# Power-1.net
KiCad netlist of a schematic drawn in Altium Designer
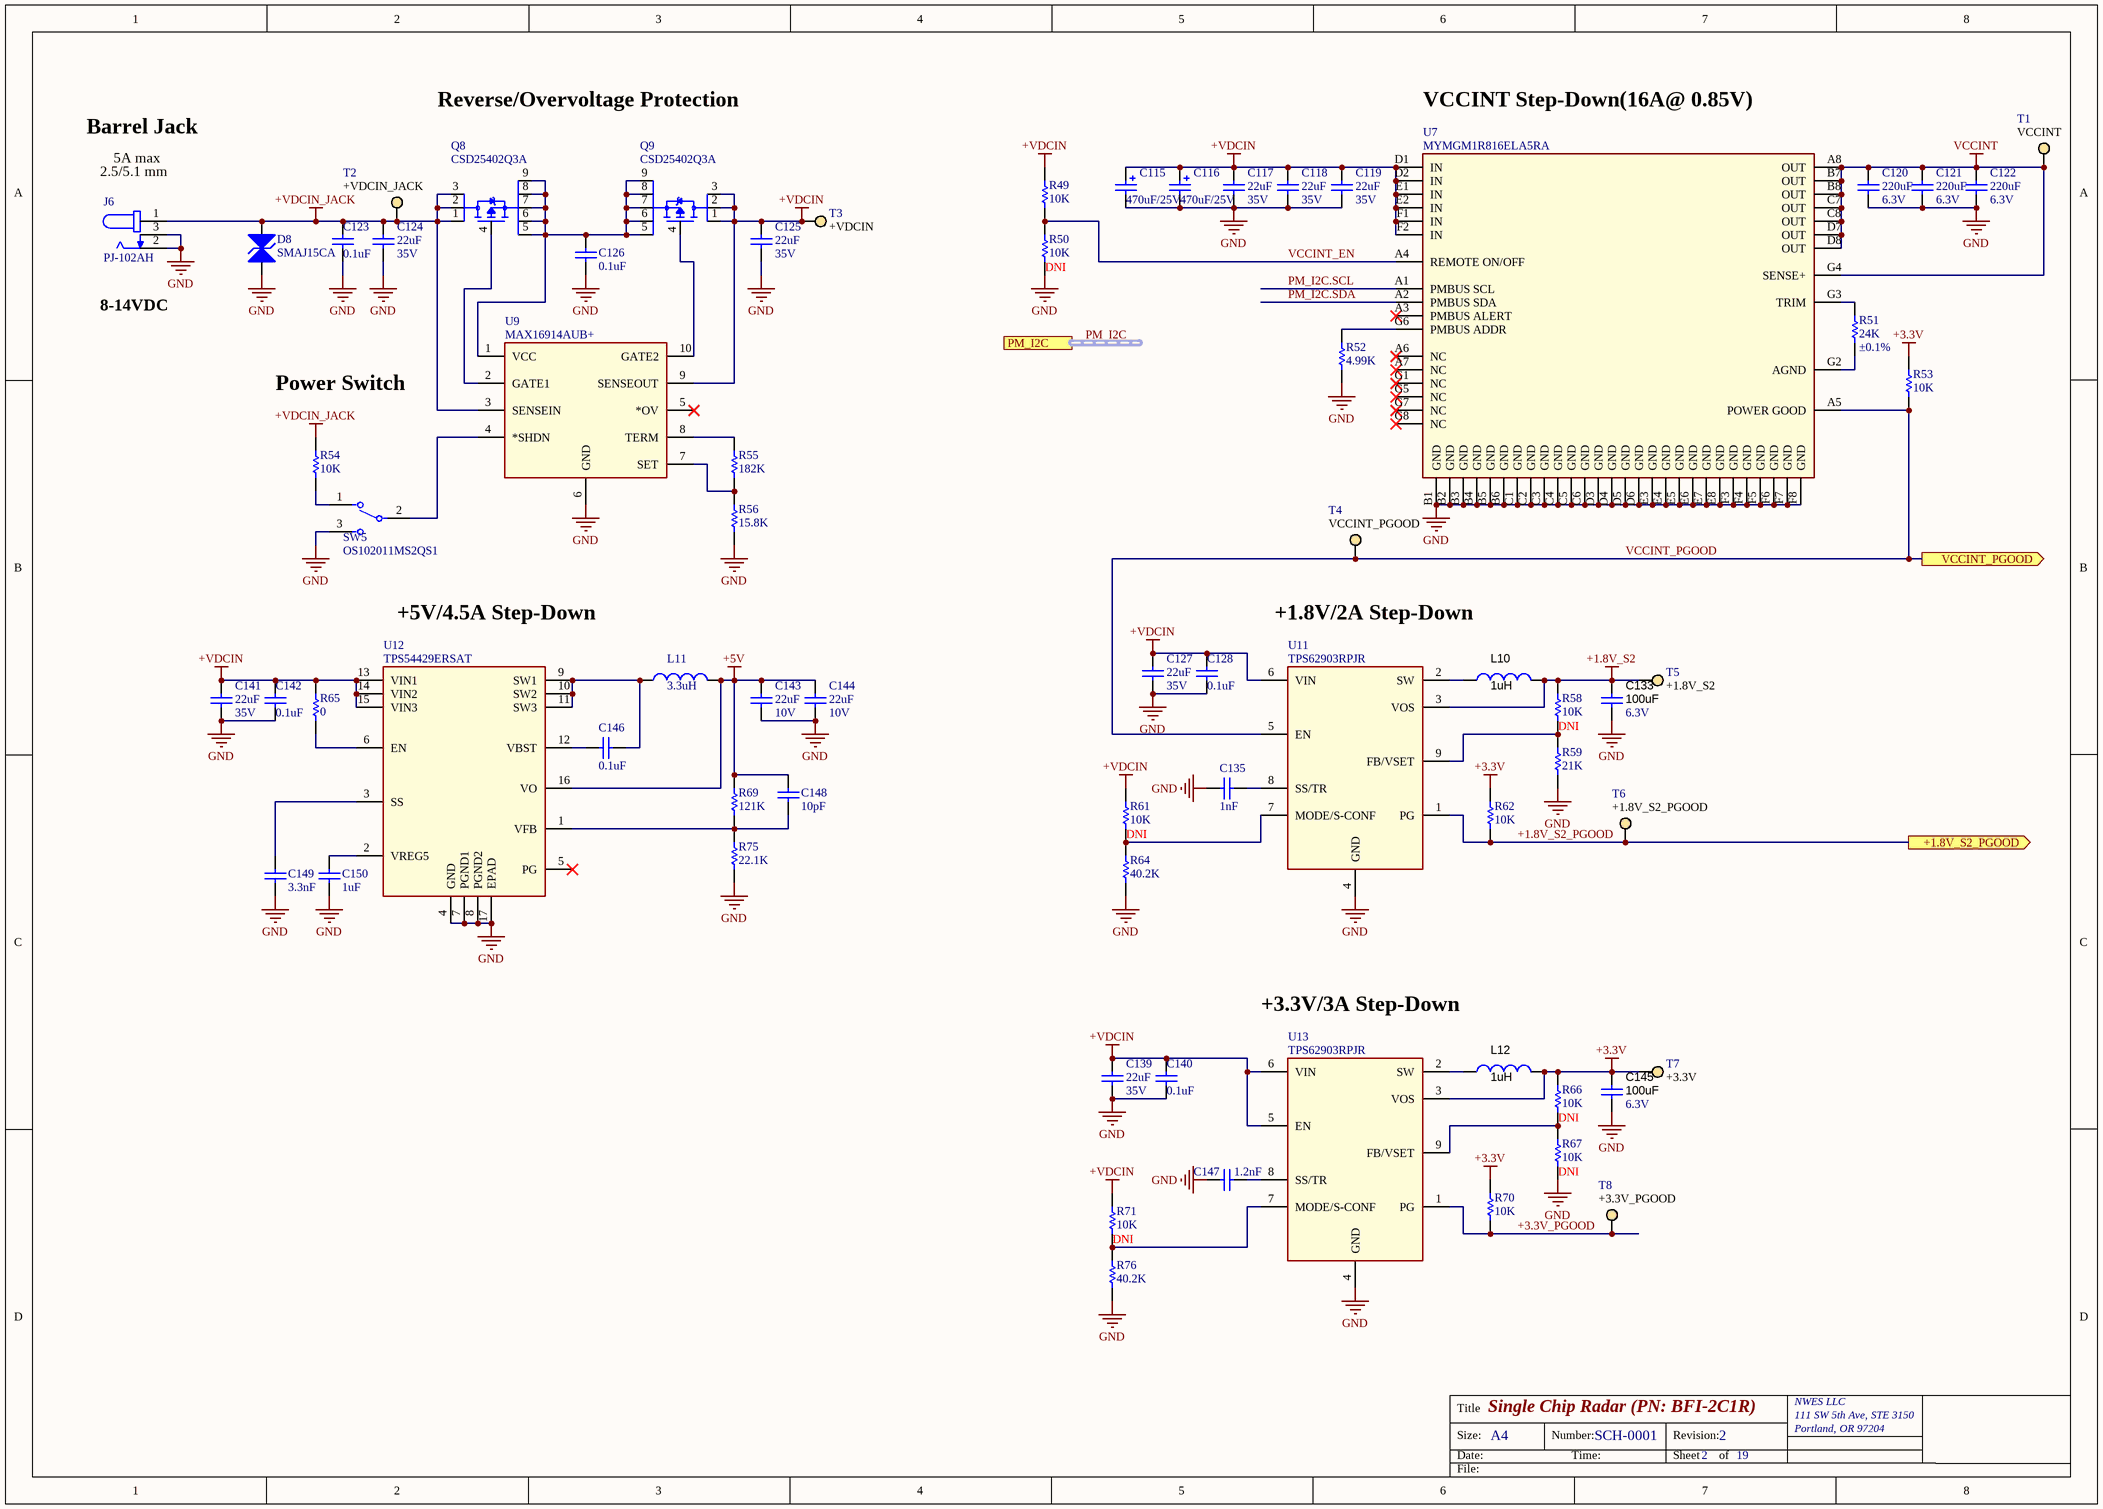
[diagram p0: Power-1.SchDoc]

(export (version "E")
  (design (tool "Eeschema 10.0.6"))
  (components
    (comp (ref "C115")
      (value "470uF/25V")
      (footprint "Panasonic EEE Size G")
      (description "Conductive Polymer Hybrid Aluminum Electrolytic Capacitors, 470µF, 25V, -55 to 125¡C")
      (fields
        (field (name "MANUFACTURER") "Panasonic")
        (field (name "MANUFACTURER PART NUMBER") "EEHZK1E471P")
      )
      (libsource (lib "Radar FPGA RF") (part "CAP ALUM POLY 470UF 20% 25V SMD"))
    )
    (comp (ref "C116")
      (value "470uF/25V")
      (footprint "Panasonic EEE Size G")
      (description "Conductive Polymer Hybrid Aluminum Electrolytic Capacitors, 470µF, 25V, -55 to 125¡C")
      (fields
        (field (name "MANUFACTURER") "Panasonic")
        (field (name "MANUFACTURER PART NUMBER") "EEHZK1E471P")
      )
      (libsource (lib "Radar FPGA RF") (part "CAP ALUM POLY 470UF 20% 25V SMD"))
    )
    (comp (ref "C117")
      (value "22uF")
      (footprint "CAPC3216X180N")
      (description "C Series 1206 22 uF 35 V ±20 % Tolerance X5R SMT Multilayer Ceramic Capacitor")
      (fields
        (field (name "MANUFACTURER") "TDK")
        (field (name "MANUFACTURER PART NUMBER") "C3216X5R1V226M160AC")
        (field (name "VOLTAGE RATING") "35V")
      )
      (libsource (lib "Radar FPGA RF") (part "CAP CER 22UF 35V X5R 1206"))
    )
    (comp (ref "C118")
      (value "22uF")
      (footprint "CAPC3216X180N")
      (description "C Series 1206 22 uF 35 V ±20 % Tolerance X5R SMT Multilayer Ceramic Capacitor")
      (fields
        (field (name "MANUFACTURER") "TDK")
        (field (name "MANUFACTURER PART NUMBER") "C3216X5R1V226M160AC")
        (field (name "VOLTAGE RATING") "35V")
      )
      (libsource (lib "Radar FPGA RF") (part "CAP CER 22UF 35V X5R 1206"))
    )
    (comp (ref "C119")
      (value "22uF")
      (footprint "CAPC3216X180N")
      (description "C Series 1206 22 uF 35 V ±20 % Tolerance X5R SMT Multilayer Ceramic Capacitor")
      (fields
        (field (name "MANUFACTURER") "TDK")
        (field (name "MANUFACTURER PART NUMBER") "C3216X5R1V226M160AC")
        (field (name "VOLTAGE RATING") "35V")
      )
      (libsource (lib "Radar FPGA RF") (part "CAP CER 22UF 35V X5R 1206"))
    )
    (comp (ref "C120")
      (value "220uF")
      (footprint "CAPC3216X180N")
      (description "1206 220 uF 6.3 V ±20% Tolernace X5R Multilayer Ceramic Capacitor")
      (fields
        (field (name "MANUFACTURER") "Murata")
        (field (name "MANUFACTURER PART NUMBER") "GRM31CR60J227ME11L")
        (field (name "VOLTAGE RATING (DC)") "6.3V")
      )
      (libsource (lib "Radar FPGA RF") (part "CAP CER 220UF 6.3V X5R 1206"))
    )
    (comp (ref "C121")
      (value "220uF")
      (footprint "CAPC3216X180N")
      (description "1206 220 uF 6.3 V ±20% Tolernace X5R Multilayer Ceramic Capacitor")
      (fields
        (field (name "MANUFACTURER") "Murata")
        (field (name "MANUFACTURER PART NUMBER") "GRM31CR60J227ME11L")
        (field (name "VOLTAGE RATING (DC)") "6.3V")
      )
      (libsource (lib "Radar FPGA RF") (part "CAP CER 220UF 6.3V X5R 1206"))
    )
    (comp (ref "C122")
      (value "220uF")
      (footprint "CAPC3216X180N")
      (description "1206 220 uF 6.3 V ±20% Tolernace X5R Multilayer Ceramic Capacitor")
      (fields
        (field (name "MANUFACTURER") "Murata")
        (field (name "MANUFACTURER PART NUMBER") "GRM31CR60J227ME11L")
        (field (name "VOLTAGE RATING (DC)") "6.3V")
      )
      (libsource (lib "Radar FPGA RF") (part "CAP CER 220UF 6.3V X5R 1206"))
    )
    (comp (ref "C123")
      (value "0.1uF")
      (footprint "CAPC1005X55USR")
      (description "CAP CER 0.1UF 25V X5R 0402")
      (fields
        (field (name "MANUFACTURER PART NUMBER") "CL05A104KA5NNNC")
        (field (name "MANUFACTURER") "Samsung Electro-Mechanics")
      )
      (libsource (lib "Radar FPGA RF") (part "CAP CER 0.1UF 25V X5R 0402"))
    )
    (comp (ref "C124")
      (value "22uF")
      (footprint "CAPC3216X180N")
      (description "C Series 1206 22 uF 35 V ±20 % Tolerance X5R SMT Multilayer Ceramic Capacitor")
      (fields
        (field (name "MANUFACTURER") "TDK")
        (field (name "MANUFACTURER PART NUMBER") "C3216X5R1V226M160AC")
        (field (name "VOLTAGE RATING") "35V")
      )
      (libsource (lib "Radar FPGA RF") (part "CAP CER 22UF 35V X5R 1206"))
    )
    (comp (ref "C125")
      (value "22uF")
      (footprint "CAPC3216X180N")
      (description "C Series 1206 22 uF 35 V ±20 % Tolerance X5R SMT Multilayer Ceramic Capacitor")
      (fields
        (field (name "MANUFACTURER") "TDK")
        (field (name "MANUFACTURER PART NUMBER") "C3216X5R1V226M160AC")
        (field (name "VOLTAGE RATING") "35V")
      )
      (libsource (lib "Radar FPGA RF") (part "CAP CER 22UF 35V X5R 1206"))
    )
    (comp (ref "C126")
      (value "0.1uF")
      (footprint "CAPC1005X55USR")
      (description "CAP CER 0.1UF 25V X5R 0402")
      (fields
        (field (name "MANUFACTURER PART NUMBER") "CL05A104KA5NNNC")
        (field (name "MANUFACTURER") "Samsung Electro-Mechanics")
      )
      (libsource (lib "Radar FPGA RF") (part "CAP CER 0.1UF 25V X5R 0402"))
    )
    (comp (ref "C127")
      (value "22uF")
      (footprint "CAPC3216X180N")
      (description "C Series 1206 22 uF 35 V ±20 % Tolerance X5R SMT Multilayer Ceramic Capacitor")
      (fields
        (field (name "MANUFACTURER") "TDK")
        (field (name "MANUFACTURER PART NUMBER") "C3216X5R1V226M160AC")
        (field (name "VOLTAGE RATING") "35V")
      )
      (libsource (lib "Radar FPGA RF") (part "CAP CER 22UF 35V X5R 1206"))
    )
    (comp (ref "C128")
      (value "0.1uF")
      (footprint "CAPC1005X55USR")
      (description "CAP CER 0.1UF 25V X5R 0402")
      (fields
        (field (name "MANUFACTURER PART NUMBER") "CL05A104KA5NNNC")
        (field (name "MANUFACTURER") "Samsung Electro-Mechanics")
      )
      (libsource (lib "Radar FPGA RF") (part "CAP CER 0.1UF 25V X5R 0402"))
    )
    (comp (ref "C133")
      (value "100uF")
      (footprint "CAPC3216X180N")
      (description "1206 100 uF 6.3 V ±20% Tolerance X5R SMT Multilayer Ceramic Capacitor")
      (fields
        (field (name "MANUFACTURER") "Murata")
        (field (name "MANUFACTURER PART NUMBER") "GRM31CR60J107ME39L")
        (field (name "VOLTAGE RATING (DC)") "6.3V")
      )
      (libsource (lib "Radar FPGA RF") (part "CAP CER 100UF 6.3V X5R 1206"))
    )
    (comp (ref "C135")
      (value "1nF")
      (footprint "CAPC1005X55USR")
      (description "0402 1000 pF 50 V ±5% Tolerance C0G Multilayer Ceramic Chip Capacitor")
      (fields
        (field (name "MANUFACTURER") "Murata")
        (field (name "MANUFACTURER PART NUMBER") "GRM1555C1H102JA01D")
      )
      (libsource (lib "Radar FPGA RF") (part "CAP CER 1000PF 50V C0G/NP0 0402"))
    )
    (comp (ref "C139")
      (value "22uF")
      (footprint "CAPC3216X180N")
      (description "C Series 1206 22 uF 35 V ±20 % Tolerance X5R SMT Multilayer Ceramic Capacitor")
      (fields
        (field (name "MANUFACTURER") "TDK")
        (field (name "MANUFACTURER PART NUMBER") "C3216X5R1V226M160AC")
        (field (name "VOLTAGE RATING") "35V")
      )
      (libsource (lib "Radar FPGA RF") (part "CAP CER 22UF 35V X5R 1206"))
    )
    (comp (ref "C140")
      (value "0.1uF")
      (footprint "CAPC1005X55USR")
      (description "CAP CER 0.1UF 25V X5R 0402")
      (fields
        (field (name "MANUFACTURER PART NUMBER") "CL05A104KA5NNNC")
        (field (name "MANUFACTURER") "Samsung Electro-Mechanics")
      )
      (libsource (lib "Radar FPGA RF") (part "CAP CER 0.1UF 25V X5R 0402"))
    )
    (comp (ref "C141")
      (value "22uF")
      (footprint "CAPC3216X180N")
      (description "C Series 1206 22 uF 35 V ±20 % Tolerance X5R SMT Multilayer Ceramic Capacitor")
      (fields
        (field (name "MANUFACTURER") "TDK")
        (field (name "MANUFACTURER PART NUMBER") "C3216X5R1V226M160AC")
        (field (name "VOLTAGE RATING") "35V")
      )
      (libsource (lib "Radar FPGA RF") (part "CAP CER 22UF 35V X5R 1206"))
    )
    (comp (ref "C142")
      (value "0.1uF")
      (footprint "CAPC1005X55USR")
      (description "CAP CER 0.1UF 25V X5R 0402")
      (fields
        (field (name "MANUFACTURER PART NUMBER") "CL05A104KA5NNNC")
        (field (name "MANUFACTURER") "Samsung Electro-Mechanics")
      )
      (libsource (lib "Radar FPGA RF") (part "CAP CER 0.1UF 25V X5R 0402"))
    )
    (comp (ref "C143")
      (value "22uF")
      (footprint "CAPC1608X100N")
      (description "Multilayer Ceramic Capacitor, 22 uF, 10 V, ± 20%, X5R, 0603 [1608 Metric]")
      (fields
        (field (name "MANUFACTURER") "TDK")
        (field (name "MANUFACTURER PART NUMBER") "C1608X5R1A226M080AC")
        (field (name "VOLTAGE RATING") "10V")
      )
      (libsource (lib "Radar FPGA RF") (part "CAP CER 22UF 10V X5R 0603"))
    )
    (comp (ref "C144")
      (value "22uF")
      (footprint "CAPC1608X100N")
      (description "Multilayer Ceramic Capacitor, 22 uF, 10 V, ± 20%, X5R, 0603 [1608 Metric]")
      (fields
        (field (name "MANUFACTURER") "TDK")
        (field (name "MANUFACTURER PART NUMBER") "C1608X5R1A226M080AC")
        (field (name "VOLTAGE RATING") "10V")
      )
      (libsource (lib "Radar FPGA RF") (part "CAP CER 22UF 10V X5R 0603"))
    )
    (comp (ref "C145")
      (value "100uF")
      (footprint "CAPC3216X180N")
      (description "1206 100 uF 6.3 V ±20% Tolerance X5R SMT Multilayer Ceramic Capacitor")
      (fields
        (field (name "MANUFACTURER") "Murata")
        (field (name "MANUFACTURER PART NUMBER") "GRM31CR60J107ME39L")
        (field (name "VOLTAGE RATING (DC)") "6.3V")
      )
      (libsource (lib "Radar FPGA RF") (part "CAP CER 100UF 6.3V X5R 1206"))
    )
    (comp (ref "C146")
      (value "0.1uF")
      (footprint "CAPC1005X55USR")
      (description "CAP CER 0.1UF 25V X5R 0402")
      (fields
        (field (name "MANUFACTURER PART NUMBER") "CL05A104KA5NNNC")
        (field (name "MANUFACTURER") "Samsung Electro-Mechanics")
      )
      (libsource (lib "Radar FPGA RF") (part "CAP CER 0.1UF 25V X5R 0402"))
    )
    (comp (ref "C147")
      (value "1.2nF")
      (footprint "CAPC1005X55USR")
      (description "0402 1.2 nF 50 V ±10% Tolerance X7R SMT Multilayer Ceramic Capacitor")
      (fields
        (field (name "MANUFACTURER") "Murata")
        (field (name "MANUFACTURER PART NUMBER") "GRM155R71H122KA01D")
      )
      (libsource (lib "Radar FPGA RF") (part "CAP CER 1200PF 50V X7R 0402"))
    )
    (comp (ref "C148")
      (value "10pF")
      (footprint "CAPC1005X55USR")
      (description "0402 10 pF 50 V ±5% Tolerance C0G SMT Multilayer Ceramic Capacitor")
      (fields
        (field (name "MANUFACTURER") "Murata")
        (field (name "MANUFACTURER PART NUMBER") "GRM1555C1H100JA01D")
      )
      (libsource (lib "Radar FPGA RF") (part "CAP CER 10PF 50V C0G/NP0 0402"))
    )
    (comp (ref "C149")
      (value "3.3nF")
      (footprint "CAPC1005X55USR")
      (description "0402 3.3 nF 50 V ±10% Tolerance X7R SMT Multilayer Ceramic Capacitor")
      (fields
        (field (name "MANUFACTURER") "Murata")
        (field (name "MANUFACTURER PART NUMBER") "GRM155R71H332KA01D")
      )
      (libsource (lib "Radar FPGA RF") (part "CAP CER 3300PF 50V X7R 0402"))
    )
    (comp (ref "C150")
      (value "1uF")
      (footprint "CAPC1005X55USR")
      (description "CAP CER 1UF 25V X5R 0402")
      (fields
        (field (name "MANUFACTURER PART NUMBER") "GRM155R61E105MA12D")
        (field (name "MANUFACTURER") "Murata Electronics")
      )
      (libsource (lib "Radar FPGA RF") (part "CAP CER 1UF 25V X5R 0402"))
    )
    (comp (ref "D8")
      (value "SMAJ15CA")
      (footprint "DIODE DO-214AC(SMA)")
      (description "Diode TVS Single Uni-Dir/Bi-Dir 15V 400W 2-Pin SMA Carrier T/R")
      (fields (field (name "MANUFACTURER") "Littelfuse"))
      (libsource (lib "XEM8320") (part "D_TVS_SMAJ15CA"))
    )
    (comp (ref "J6")
      (value "PJ-102AH")
      (footprint "CUI_PJ-102AH")
      (description "2.0 x 6.5 mm, 5.0 A, Horizontal, Through Hole, Tapered Pins, Dc Power Jack Connector")
      (fields (field (name "MANUFACTURER") "CUI"))
      (libsource (lib "XEM8320") (part "PJ-102AH"))
    )
    (comp (ref "L10")
      (value "1uH")
      (footprint "DFE252012P")
      (description "Inductor Power Chip Shielded Wirewound 1uH 20% 1MHz Metal 3.3A 0.04Ohm DCR 1008 T/R")
      (fields
        (field (name "MANUFACTURER") "Murata")
        (field (name "MANUFACTURER PART NUMBER") "DFE252012F-1R0M=P2")
      )
      (libsource (lib "Radar FPGA RF") (part "FIXED IND 1UH 3.3A 40 MOHM SMD"))
    )
    (comp (ref "L11")
      (value "3.3uH")
      (footprint "IND_IHLP-3232DZ_VIS")
      (description "Inductor Power Shielded Wirewound 3.3uH 20% 100KHz Powdered Iron 9.2A 17.7mOhm DCR 3232 T/R")
      (fields
        (field (name "MANUFACTURER") "Vishay Dale")
        (field (name "MANUFACTURER PART NUMBER") "IHLP3232DZER3R3M01")
        (field (name "INDUCTANCE") "3.3uH")
      )
      (libsource (lib "Radar FPGA RF") (part "FIXED IND 3.3UH 9.2A 17.7MOHM SM"))
    )
    (comp (ref "L12")
      (value "1uH")
      (footprint "DFE252012P")
      (description "Inductor Power Chip Shielded Wirewound 1uH 20% 1MHz Metal 3.3A 0.04Ohm DCR 1008 T/R")
      (fields
        (field (name "MANUFACTURER") "Murata")
        (field (name "MANUFACTURER PART NUMBER") "DFE252012F-1R0M=P2")
      )
      (libsource (lib "Radar FPGA RF") (part "FIXED IND 1UH 3.3A 40 MOHM SMD"))
    )
    (comp (ref "Q8")
      (value "CSD25402Q3A")
      (footprint "8-VSONP (3x3.15)")
      (description "MOSFET P-CH 20V 72A 8SON")
      (fields (field (name "MANUFACTURER") "Texas Instruments"))
      (libsource (lib "XEM8320") (part "CSD25402Q3A"))
    )
    (comp (ref "Q9")
      (value "CSD25402Q3A")
      (footprint "8-VSONP (3x3.15)")
      (description "MOSFET P-CH 20V 72A 8SON")
      (fields (field (name "MANUFACTURER") "Texas Instruments"))
      (libsource (lib "XEM8320") (part "CSD25402Q3A"))
    )
    (comp (ref "R49")
      (value "10K")
      (footprint "RESC1005X40USR")
      (description "RES 10K OHM 1% 1/16W 0402")
      (fields
        (field (name "MANUFACTURER") "YAGEO")
        (field (name "MANUFACTURER PART NUMBER") "RC0402FR-0710KL")
      )
      (libsource (lib "Radar FPGA RF") (part "RES 10K OHM 1% 1/16W 0402"))
    )
    (comp (ref "R50")
      (value "10K")
      (footprint "RESC1005X40USR")
      (description "RES 10K OHM 1% 1/16W 0402")
      (fields
        (field (name "MANUFACTURER") "YAGEO")
        (field (name "MANUFACTURER PART NUMBER") "RC0402FR-0710KL")
      )
      (libsource (lib "Radar FPGA RF") (part "RES 10K OHM 1% 1/16W 0402"))
    )
    (comp (ref "R51")
      (value "24K")
      (footprint "RESC1005X40USR")
      (description "RES SMD 24K OHM 0.1% 1/16W 0402")
      (fields
        (field (name "MANUFACTURER") "YAGEO")
        (field (name "MANUFACTURER PART NUMBER") "RT0402BRE0724KL")
        (field (name "TOLERANCE") "±0.1%")
      )
      (libsource (lib "Radar FPGA RF") (part "RES 24K OHM 0.1% 1/16W 0402"))
    )
    (comp (ref "R52")
      (value "4.99K")
      (footprint "RESC1005X40USR")
      (description "RES 4.99K OHM 1% 1/16W 0402")
      (fields
        (field (name "MANUFACTURER") "YAGEO")
        (field (name "MANUFACTURER PART NUMBER") "RC0402FR-074K99L")
      )
      (libsource (lib "Radar FPGA RF") (part "RES 4.99K OHM 1% 1/16W 0402"))
    )
    (comp (ref "R53")
      (value "10K")
      (footprint "RESC1005X40USR")
      (description "RES 10K OHM 1% 1/16W 0402")
      (fields
        (field (name "MANUFACTURER") "YAGEO")
        (field (name "MANUFACTURER PART NUMBER") "RC0402FR-0710KL")
      )
      (libsource (lib "Radar FPGA RF") (part "RES 10K OHM 1% 1/16W 0402"))
    )
    (comp (ref "R54")
      (value "10K")
      (footprint "RESC1005X40USR")
      (description "RES 10K OHM 1% 1/16W 0402")
      (fields
        (field (name "MANUFACTURER") "YAGEO")
        (field (name "MANUFACTURER PART NUMBER") "RC0402FR-0710KL")
      )
      (libsource (lib "Radar FPGA RF") (part "RES 10K OHM 1% 1/16W 0402"))
    )
    (comp (ref "R55")
      (value "182K")
      (footprint "RESC1005X40USR")
      (description "RES 182K OHM 1% 1/16W 0402")
      (fields
        (field (name "MANUFACTURER") "YAGEO")
        (field (name "MANUFACTURER PART NUMBER") "RC0402FR-07182KL")
      )
      (libsource (lib "Radar FPGA RF") (part "RES 182K OHM 1% 1/16W 0402"))
    )
    (comp (ref "R56")
      (value "15.8K")
      (footprint "RESC1005X40USR")
      (description "RES 15.8K OHM 1% 1/16W 0402")
      (fields
        (field (name "MANUFACTURER") "YAGEO")
        (field (name "MANUFACTURER PART NUMBER") "RC0402FR-0715K8L")
      )
      (libsource (lib "Radar FPGA RF") (part "RES 15.8K OHM 1% 1/16W 0402"))
    )
    (comp (ref "R58")
      (value "10K")
      (footprint "RESC1005X40USR")
      (description "RES 10K OHM 1% 1/16W 0402")
      (fields
        (field (name "MANUFACTURER") "YAGEO")
        (field (name "MANUFACTURER PART NUMBER") "RC0402FR-0710KL")
      )
      (libsource (lib "Radar FPGA RF") (part "RES 10K OHM 1% 1/16W 0402"))
    )
    (comp (ref "R59")
      (value "21K")
      (footprint "RESC1005X40USR")
      (description "RES 21K OHM 1% 1/16W 0402")
      (fields
        (field (name "MANUFACTURER") "YAGEO")
        (field (name "MANUFACTURER PART NUMBER") "RC0402FR-0721KL")
      )
      (libsource (lib "Radar FPGA RF") (part "RES 21K OHM 1% 1/16W 0402"))
    )
    (comp (ref "R61")
      (value "10K")
      (footprint "RESC1005X40USR")
      (description "RES 10K OHM 1% 1/16W 0402")
      (fields
        (field (name "MANUFACTURER") "YAGEO")
        (field (name "MANUFACTURER PART NUMBER") "RC0402FR-0710KL")
      )
      (libsource (lib "Radar FPGA RF") (part "RES 10K OHM 1% 1/16W 0402"))
    )
    (comp (ref "R62")
      (value "10K")
      (footprint "RESC1005X40USR")
      (description "RES 10K OHM 1% 1/16W 0402")
      (fields
        (field (name "MANUFACTURER") "YAGEO")
        (field (name "MANUFACTURER PART NUMBER") "RC0402FR-0710KL")
      )
      (libsource (lib "Radar FPGA RF") (part "RES 10K OHM 1% 1/16W 0402"))
    )
    (comp (ref "R64")
      (value "40.2K")
      (footprint "RESC1005X40USR")
      (description "RES 40.2K OHM 1% 1/16W 0402")
      (fields
        (field (name "MANUFACTURER") "YAGEO")
        (field (name "MANUFACTURER PART NUMBER") "RC0402FR-0740K2L")
      )
      (libsource (lib "Radar FPGA RF") (part "RES 40.2K OHM 1% 1/16W 0402"))
    )
    (comp (ref "R65")
      (value "0")
      (footprint "RESC1005X40USR")
      (description "RES 0 OHM JUMPER 1/16W 0402")
      (fields
        (field (name "MANUFACTURER") "Yageo")
        (field (name "MANUFACTURER PART NUMBER") "RC0402JR-070RL")
      )
      (libsource (lib "Radar FPGA RF") (part "RES 0 OHM JUMPER 1/16W 0402"))
    )
    (comp (ref "R66")
      (value "10K")
      (footprint "RESC1005X40USR")
      (description "RES 10K OHM 1% 1/16W 0402")
      (fields
        (field (name "MANUFACTURER") "YAGEO")
        (field (name "MANUFACTURER PART NUMBER") "RC0402FR-0710KL")
      )
      (libsource (lib "Radar FPGA RF") (part "RES 10K OHM 1% 1/16W 0402"))
    )
    (comp (ref "R67")
      (value "10K")
      (footprint "RESC1005X40USR")
      (description "RES 10K OHM 1% 1/16W 0402")
      (fields
        (field (name "MANUFACTURER") "YAGEO")
        (field (name "MANUFACTURER PART NUMBER") "RC0402FR-0710KL")
      )
      (libsource (lib "Radar FPGA RF") (part "RES 10K OHM 1% 1/16W 0402"))
    )
    (comp (ref "R69")
      (value "121K")
      (footprint "RESC1005X40USR")
      (description "RES 121K OHM 1% 1/16W 0402")
      (fields
        (field (name "MANUFACTURER") "YAGEO")
        (field (name "MANUFACTURER PART NUMBER") "RC0402FR-07121KL")
      )
      (libsource (lib "Radar FPGA RF") (part "RES 121K OHM 1% 1/16W 0402"))
    )
    (comp (ref "R70")
      (value "10K")
      (footprint "RESC1005X40USR")
      (description "RES 10K OHM 1% 1/16W 0402")
      (fields
        (field (name "MANUFACTURER") "YAGEO")
        (field (name "MANUFACTURER PART NUMBER") "RC0402FR-0710KL")
      )
      (libsource (lib "Radar FPGA RF") (part "RES 10K OHM 1% 1/16W 0402"))
    )
    (comp (ref "R71")
      (value "10K")
      (footprint "RESC1005X40USR")
      (description "RES 10K OHM 1% 1/16W 0402")
      (fields
        (field (name "MANUFACTURER") "YAGEO")
        (field (name "MANUFACTURER PART NUMBER") "RC0402FR-0710KL")
      )
      (libsource (lib "Radar FPGA RF") (part "RES 10K OHM 1% 1/16W 0402"))
    )
    (comp (ref "R75")
      (value "22.1K")
      (footprint "RESC1005X40USR")
      (description "RES 22.1K OHM 1% 1/16W 0402")
      (fields
        (field (name "MANUFACTURER") "YAGEO")
        (field (name "MANUFACTURER PART NUMBER") "RC0402FR-0722K1L")
      )
      (libsource (lib "Radar FPGA RF") (part "RES 22.1K OHM 1% 1/16W 0402"))
    )
    (comp (ref "R76")
      (value "40.2K")
      (footprint "RESC1005X40USR")
      (description "RES 40.2K OHM 1% 1/16W 0402")
      (fields
        (field (name "MANUFACTURER") "YAGEO")
        (field (name "MANUFACTURER PART NUMBER") "RC0402FR-0740K2L")
      )
      (libsource (lib "Radar FPGA RF") (part "RES 40.2K OHM 1% 1/16W 0402"))
    )
    (comp (ref "SW5")
      (value "OS102011MS2QS1")
      (footprint "SW_OS102011MS2QS1")
      (description "Switch Slide ON ON SPDT Top Slide 0.1A 12VDC 10000Cycle PC Pins Bracket Mount/Through Hole Bulk")
      (fields (field (name "MANUFACTURER") "ITT C&K"))
      (libsource (lib "XEM8320") (part "SW_OS102011MS2QS1"))
    )
    (comp (ref "T1")
      (value "TP_S")
      (footprint "TP_SM_1MM")
      (description "test point")
      (fields (field (name "PARAMETER 1") "VCCINT"))
      (libsource (lib "Radar FPGA RF") (part "Test point PAD"))
    )
    (comp (ref "T2")
      (value "TP_S")
      (footprint "TP_SM_1MM")
      (description "test point")
      (fields (field (name "PARAMETER 1") "+VDCIN_JACK"))
      (libsource (lib "Radar FPGA RF") (part "Test point PAD"))
    )
    (comp (ref "T3")
      (value "TP_S")
      (footprint "TP_SM_1MM")
      (description "test point")
      (fields (field (name "PARAMETER 1") "+VDCIN"))
      (libsource (lib "Radar FPGA RF") (part "Test point PAD"))
    )
    (comp (ref "T4")
      (value "TP_S")
      (footprint "TP_SM_1MM")
      (description "test point")
      (fields (field (name "PARAMETER 1") "VCCINT_PGOOD"))
      (libsource (lib "Radar FPGA RF") (part "Test point PAD"))
    )
    (comp (ref "T5")
      (value "TP_S")
      (footprint "TP_SM_1MM")
      (description "test point")
      (fields (field (name "PARAMETER 1") "+1.8V_S2"))
      (libsource (lib "Radar FPGA RF") (part "Test point PAD"))
    )
    (comp (ref "T6")
      (value "TP_S")
      (footprint "TP_SM_1MM")
      (description "test point")
      (fields (field (name "PARAMETER 1") "+1.8V_S2_PGOOD"))
      (libsource (lib "Radar FPGA RF") (part "Test point PAD"))
    )
    (comp (ref "T7")
      (value "TP_S")
      (footprint "TP_SM_1MM")
      (description "test point")
      (fields (field (name "PARAMETER 1") "+3.3V"))
      (libsource (lib "Radar FPGA RF") (part "Test point PAD"))
    )
    (comp (ref "T8")
      (value "TP_S")
      (footprint "TP_SM_1MM")
      (description "test point")
      (fields (field (name "PARAMETER 1") "+3.3V_PGOOD"))
      (libsource (lib "Radar FPGA RF") (part "Test point PAD"))
    )
    (comp (ref "U7")
      (value "MYMGM1R816ELA5RA")
      (footprint "56-SMD Module")
      (description "Non-Isolated PoL Module DC DC Converter 1 Output 0.7 ~ 1.8V 16A 7.5V - 15V Input")
      (fields (field (name "MANUFACTURER") "Murata"))
      (libsource (lib "XEM8320") (part "MYMGM1R816ELA5RA"))
    )
    (comp (ref "U9")
      (value "MAX16914AUB+")
      (footprint "10-TFSOP")
      (description "Ideal Diode, Reverse-Battery, and Overvoltage Protection Switch/Limiter Controll")
      (fields (field (name "MANUFACTURER") "Maxim"))
      (libsource (lib "XEM8320") (part "MAX16914AUB+"))
    )
    (comp (ref "U11")
      (value "TPS62903RPJR")
      (footprint "9-VQFN-HR (1.5x2)")
      (description "3-V TO 17-V, 3-A, HIGH-EFFICIENC")
      (fields (field (name "MANUFACTURER") "Texas Instruments"))
      (libsource (lib "XEM8320") (part "TPS62903RPJR"))
    )
    (comp (ref "U12")
      (value "TPS54429ERSAT")
      (footprint "16-QFN (4x4)")
      (description "IC REG BUCK ADJ 4.5A 16QFN")
      (fields (field (name "MANUFACTURER") "Texas Instruments"))
      (libsource (lib "XEM8320") (part "TPS54429ERSAT"))
    )
    (comp (ref "U13")
      (value "TPS62903RPJR")
      (footprint "9-VQFN-HR (1.5x2)")
      (description "3-V TO 17-V, 3-A, HIGH-EFFICIENC")
      (fields (field (name "MANUFACTURER") "Texas Instruments"))
      (libsource (lib "XEM8320") (part "TPS62903RPJR"))
    )
  )
  (nets
    (net (code "2") (name "+1.8V_S2") (class "Default")
      (node (ref "C133") (pin "1") (pinfunction "1_1") (pintype "passive"))
      (node (ref "L10") (pin "2") (pinfunction "2_2") (pintype "passive"))
      (node (ref "R58") (pin "2") (pinfunction "2_2") (pintype "passive"))
      (node (ref "T5") (pin "1") (pintype "passive"))
      (node (ref "U11") (pin "3") (pinfunction "VOS_3") (pintype "passive"))
    )
    (net (code "3") (name "+3.3V") (class "Default")
      (node (ref "C145") (pin "1") (pinfunction "1_1") (pintype "passive"))
      (node (ref "L12") (pin "2") (pinfunction "2_2") (pintype "passive"))
      (node (ref "R53") (pin "2") (pinfunction "2_2") (pintype "passive"))
      (node (ref "R62") (pin "2") (pinfunction "2_2") (pintype "passive"))
      (node (ref "R66") (pin "2") (pinfunction "2_2") (pintype "passive"))
      (node (ref "R70") (pin "2") (pinfunction "2_2") (pintype "passive"))
      (node (ref "T7") (pin "1") (pintype "passive"))
      (node (ref "U13") (pin "3") (pinfunction "VOS_3") (pintype "passive"))
    )
    (net (code "4") (name "+5V") (class "Default")
      (node (ref "C143") (pin "1") (pinfunction "1_1") (pintype "passive"))
      (node (ref "C144") (pin "1") (pinfunction "1_1") (pintype "passive"))
      (node (ref "C148") (pin "2") (pinfunction "2_2") (pintype "passive"))
      (node (ref "L11") (pin "2") (pinfunction "2_2") (pintype "passive"))
      (node (ref "R69") (pin "2") (pinfunction "2_2") (pintype "passive"))
      (node (ref "U12") (pin "16") (pinfunction "VO_16") (pintype "passive"))
    )
    (net (code "5") (name "+VDCIN") (class "Default")
      (node (ref "C115") (pin "1") (pinfunction "1_1") (pintype "passive"))
      (node (ref "C116") (pin "1") (pinfunction "1_1") (pintype "passive"))
      (node (ref "C117") (pin "1") (pinfunction "1_1") (pintype "passive"))
      (node (ref "C118") (pin "1") (pinfunction "1_1") (pintype "passive"))
      (node (ref "C119") (pin "1") (pinfunction "1_1") (pintype "passive"))
      (node (ref "C125") (pin "1") (pinfunction "1_1") (pintype "passive"))
      (node (ref "C127") (pin "1") (pinfunction "1_1") (pintype "passive"))
      (node (ref "C128") (pin "2") (pinfunction "2_2") (pintype "passive"))
      (node (ref "C139") (pin "1") (pinfunction "1_1") (pintype "passive"))
      (node (ref "C140") (pin "2") (pinfunction "2_2") (pintype "passive"))
      (node (ref "C141") (pin "1") (pinfunction "1_1") (pintype "passive"))
      (node (ref "C142") (pin "2") (pinfunction "2_2") (pintype "passive"))
      (node (ref "Q9") (pin "1") (pinfunction "D_1") (pintype "passive"))
      (node (ref "Q9") (pin "2") (pinfunction "D_2") (pintype "passive"))
      (node (ref "Q9") (pin "3") (pinfunction "D_3") (pintype "passive"))
      (node (ref "R49") (pin "2") (pinfunction "2_2") (pintype "passive"))
      (node (ref "R61") (pin "2") (pinfunction "2_2") (pintype "passive"))
      (node (ref "R65") (pin "2") (pinfunction "2_2") (pintype "passive"))
      (node (ref "R71") (pin "2") (pinfunction "2_2") (pintype "passive"))
      (node (ref "T3") (pin "1") (pintype "passive"))
      (node (ref "U11") (pin "6") (pinfunction "VIN_6") (pintype "passive"))
      (node (ref "U12") (pin "13") (pinfunction "VIN1_13") (pintype "passive"))
      (node (ref "U12") (pin "14") (pinfunction "VIN2_14") (pintype "passive"))
      (node (ref "U12") (pin "15") (pinfunction "VIN3_15") (pintype "passive"))
      (node (ref "U13") (pin "5") (pinfunction "EN_5") (pintype "passive"))
      (node (ref "U13") (pin "6") (pinfunction "VIN_6") (pintype "passive"))
      (node (ref "U7") (pin "D1") (pinfunction "IN_D1") (pintype "passive"))
      (node (ref "U7") (pin "D2") (pinfunction "IN_D2") (pintype "passive"))
      (node (ref "U7") (pin "E1") (pinfunction "IN_E1") (pintype "passive"))
      (node (ref "U7") (pin "E2") (pinfunction "IN_E2") (pintype "passive"))
      (node (ref "U7") (pin "F1") (pinfunction "IN_F1") (pintype "passive"))
      (node (ref "U7") (pin "F2") (pinfunction "IN_F2") (pintype "passive"))
      (node (ref "U9") (pin "9") (pinfunction "SENSEOUT_9") (pintype "passive"))
    )
    (net (code "6") (name "+VDCIN_JACK") (class "Default")
      (node (ref "C123") (pin "2") (pinfunction "2_2") (pintype "passive"))
      (node (ref "C124") (pin "1") (pinfunction "1_1") (pintype "passive"))
      (node (ref "D8") (pin "1") (pinfunction "1_1") (pintype "passive"))
      (node (ref "J6") (pin "1") (pinfunction "1_1") (pintype "passive"))
      (node (ref "Q8") (pin "1") (pinfunction "D_1") (pintype "passive"))
      (node (ref "Q8") (pin "2") (pinfunction "D_2") (pintype "passive"))
      (node (ref "Q8") (pin "3") (pinfunction "D_3") (pintype "passive"))
      (node (ref "R54") (pin "2") (pinfunction "2_2") (pintype "passive"))
      (node (ref "T2") (pin "1") (pintype "passive"))
      (node (ref "U9") (pin "3") (pinfunction "SENSEIN_3") (pintype "passive"))
    )
    (net (code "7") (name "/+1.8V_S2_PGOOD") (class "Default")
      (node (ref "R62") (pin "1") (pinfunction "1_1") (pintype "passive"))
      (node (ref "T6") (pin "1") (pintype "passive"))
      (node (ref "U11") (pin "1") (pinfunction "PG_1") (pintype "passive"))
    )
    (net (code "8") (name "/+3.3V_PGOOD") (class "Default")
      (node (ref "R70") (pin "1") (pinfunction "1_1") (pintype "passive"))
      (node (ref "T8") (pin "1") (pintype "passive"))
      (node (ref "U13") (pin "1") (pinfunction "PG_1") (pintype "passive"))
    )
    (net (code "9") (name "/PM_I2C.SCL") (class "Default")
      (node (ref "U7") (pin "A1") (pinfunction "PMBUS_SCL_A1") (pintype "passive"))
    )
    (net (code "10") (name "/PM_I2C.SDA") (class "Default")
      (node (ref "U7") (pin "A2") (pinfunction "PMBUS_SDA_A2") (pintype "passive"))
    )
    (net (code "11") (name "/VCCINT_EN") (class "Default")
      (node (ref "R49") (pin "1") (pinfunction "1_1") (pintype "passive"))
      (node (ref "R50") (pin "2") (pinfunction "2_2") (pintype "passive"))
      (node (ref "U7") (pin "A4") (pinfunction "REMOTE_ON/OFF_A4") (pintype "passive"))
    )
    (net (code "12") (name "/VCCINT_PGOOD") (class "Default")
      (node (ref "R53") (pin "1") (pinfunction "1_1") (pintype "passive"))
      (node (ref "T4") (pin "1") (pintype "passive"))
      (node (ref "U11") (pin "5") (pinfunction "EN_5") (pintype "passive"))
      (node (ref "U7") (pin "A5") (pinfunction "POWER_GOOD_A5") (pintype "passive"))
    )
    (net (code "14") (name "GND") (class "Default")
      (node (ref "C115") (pin "2") (pinfunction "2_2") (pintype "passive"))
      (node (ref "C116") (pin "2") (pinfunction "2_2") (pintype "passive"))
      (node (ref "C117") (pin "2") (pinfunction "2_2") (pintype "passive"))
      (node (ref "C118") (pin "2") (pinfunction "2_2") (pintype "passive"))
      (node (ref "C119") (pin "2") (pinfunction "2_2") (pintype "passive"))
      (node (ref "C120") (pin "2") (pinfunction "2_2") (pintype "passive"))
      (node (ref "C121") (pin "2") (pinfunction "2_2") (pintype "passive"))
      (node (ref "C122") (pin "2") (pinfunction "2_2") (pintype "passive"))
      (node (ref "C123") (pin "1") (pinfunction "1_1") (pintype "passive"))
      (node (ref "C124") (pin "2") (pinfunction "2_2") (pintype "passive"))
      (node (ref "C125") (pin "2") (pinfunction "2_2") (pintype "passive"))
      (node (ref "C126") (pin "1") (pinfunction "1_1") (pintype "passive"))
      (node (ref "C127") (pin "2") (pinfunction "2_2") (pintype "passive"))
      (node (ref "C128") (pin "1") (pinfunction "1_1") (pintype "passive"))
      (node (ref "C133") (pin "2") (pinfunction "2_2") (pintype "passive"))
      (node (ref "C135") (pin "1") (pinfunction "1_1") (pintype "passive"))
      (node (ref "C139") (pin "2") (pinfunction "2_2") (pintype "passive"))
      (node (ref "C140") (pin "1") (pinfunction "1_1") (pintype "passive"))
      (node (ref "C141") (pin "2") (pinfunction "2_2") (pintype "passive"))
      (node (ref "C142") (pin "1") (pinfunction "1_1") (pintype "passive"))
      (node (ref "C143") (pin "2") (pinfunction "2_2") (pintype "passive"))
      (node (ref "C144") (pin "2") (pinfunction "2_2") (pintype "passive"))
      (node (ref "C145") (pin "2") (pinfunction "2_2") (pintype "passive"))
      (node (ref "C147") (pin "1") (pinfunction "1_1") (pintype "passive"))
      (node (ref "C149") (pin "1") (pinfunction "1_1") (pintype "passive"))
      (node (ref "C150") (pin "1") (pinfunction "1_1") (pintype "passive"))
      (node (ref "D8") (pin "2") (pinfunction "2_2") (pintype "passive"))
      (node (ref "J6") (pin "2") (pinfunction "2_2") (pintype "passive"))
      (node (ref "J6") (pin "3") (pinfunction "3_3") (pintype "passive"))
      (node (ref "R50") (pin "1") (pinfunction "1_1") (pintype "passive"))
      (node (ref "R52") (pin "1") (pinfunction "1_1") (pintype "passive"))
      (node (ref "R56") (pin "1") (pinfunction "1_1") (pintype "passive"))
      (node (ref "R59") (pin "1") (pinfunction "1_1") (pintype "passive"))
      (node (ref "R64") (pin "1") (pinfunction "1_1") (pintype "passive"))
      (node (ref "R67") (pin "1") (pinfunction "1_1") (pintype "passive"))
      (node (ref "R75") (pin "1") (pinfunction "1_1") (pintype "passive"))
      (node (ref "R76") (pin "1") (pinfunction "1_1") (pintype "passive"))
      (node (ref "SW5") (pin "3") (pinfunction "3_3") (pintype "passive"))
      (node (ref "U11") (pin "4") (pinfunction "GND_4") (pintype "passive"))
      (node (ref "U12") (pin "17") (pinfunction "EPAD_17") (pintype "passive"))
      (node (ref "U12") (pin "4") (pinfunction "GND_4") (pintype "passive"))
      (node (ref "U12") (pin "7") (pinfunction "PGND1_7") (pintype "passive"))
      (node (ref "U12") (pin "8") (pinfunction "PGND2_8") (pintype "passive"))
      (node (ref "U13") (pin "4") (pinfunction "GND_4") (pintype "passive"))
      (node (ref "U7") (pin "B1") (pinfunction "GND_B1") (pintype "passive"))
      (node (ref "U7") (pin "B2") (pinfunction "GND_B2") (pintype "passive"))
      (node (ref "U7") (pin "B3") (pinfunction "GND_B3") (pintype "passive"))
      (node (ref "U7") (pin "B4") (pinfunction "GND_B4") (pintype "passive"))
      (node (ref "U7") (pin "B5") (pinfunction "GND_B5") (pintype "passive"))
      (node (ref "U7") (pin "B6") (pinfunction "GND_B6") (pintype "passive"))
      (node (ref "U7") (pin "C1") (pinfunction "GND_C1") (pintype "passive"))
      (node (ref "U7") (pin "C2") (pinfunction "GND_C2") (pintype "passive"))
      (node (ref "U7") (pin "C3") (pinfunction "GND_C3") (pintype "passive"))
      (node (ref "U7") (pin "C4") (pinfunction "GND_C4") (pintype "passive"))
      (node (ref "U7") (pin "C5") (pinfunction "GND_C5") (pintype "passive"))
      (node (ref "U7") (pin "C6") (pinfunction "GND_C6") (pintype "passive"))
      (node (ref "U7") (pin "D3") (pinfunction "GND_D3") (pintype "passive"))
      (node (ref "U7") (pin "D4") (pinfunction "GND_D4") (pintype "passive"))
      (node (ref "U7") (pin "D5") (pinfunction "GND_D5") (pintype "passive"))
      (node (ref "U7") (pin "D6") (pinfunction "GND_D6") (pintype "passive"))
      (node (ref "U7") (pin "E3") (pinfunction "GND_E3") (pintype "passive"))
      (node (ref "U7") (pin "E4") (pinfunction "GND_E4") (pintype "passive"))
      (node (ref "U7") (pin "E5") (pinfunction "GND_E5") (pintype "passive"))
      (node (ref "U7") (pin "E6") (pinfunction "GND_E6") (pintype "passive"))
      (node (ref "U7") (pin "E7") (pinfunction "GND_E7") (pintype "passive"))
      (node (ref "U7") (pin "E8") (pinfunction "GND_E8") (pintype "passive"))
      (node (ref "U7") (pin "F3") (pinfunction "GND_F3") (pintype "passive"))
      (node (ref "U7") (pin "F4") (pinfunction "GND_F4") (pintype "passive"))
      (node (ref "U7") (pin "F5") (pinfunction "GND_F5") (pintype "passive"))
      (node (ref "U7") (pin "F6") (pinfunction "GND_F6") (pintype "passive"))
      (node (ref "U7") (pin "F7") (pinfunction "GND_F7") (pintype "passive"))
      (node (ref "U7") (pin "F8") (pinfunction "GND_F8") (pintype "passive"))
      (node (ref "U9") (pin "6") (pinfunction "GND_6") (pintype "passive"))
    )
    (net (code "15") (name "Net-(Q8-G)") (class "Default")
      (node (ref "Q8") (pin "4") (pinfunction "G_4") (pintype "passive"))
      (node (ref "U9") (pin "2") (pinfunction "GATE1_2") (pintype "passive"))
    )
    (net (code "16") (name "Net-(Q9-G)") (class "Default")
      (node (ref "Q9") (pin "4") (pinfunction "G_4") (pintype "passive"))
      (node (ref "U9") (pin "10") (pinfunction "GATE2_10") (pintype "passive"))
    )
    (net (code "17") (name "Net-(R54-Pad1)") (class "Default")
      (node (ref "R54") (pin "1") (pinfunction "1_1") (pintype "passive"))
      (node (ref "SW5") (pin "1") (pinfunction "1_1") (pintype "passive"))
    )
    (net (code "18") (name "Net-(U7-AGND)") (class "Default")
      (node (ref "R51") (pin "1") (pinfunction "1_1") (pintype "passive"))
      (node (ref "U7") (pin "G2") (pinfunction "AGND_G2") (pintype "passive"))
    )
    (net (code "19") (name "Net-(U7-PMBUS_ADDR)") (class "Default")
      (node (ref "R52") (pin "2") (pinfunction "2_2") (pintype "passive"))
      (node (ref "U7") (pin "G6") (pinfunction "PMBUS_ADDR_G6") (pintype "passive"))
    )
    (net (code "20") (name "Net-(U7-TRIM)") (class "Default")
      (node (ref "R51") (pin "2") (pinfunction "2_2") (pintype "passive"))
      (node (ref "U7") (pin "G3") (pinfunction "TRIM_G3") (pintype "passive"))
    )
    (net (code "21") (name "Net-(U9-*SHDN)") (class "Default")
      (node (ref "SW5") (pin "2") (pinfunction "2_2") (pintype "passive"))
      (node (ref "U9") (pin "4") (pinfunction "*SHDN_4") (pintype "passive"))
    )
    (net (code "22") (name "Net-(U9-SET)") (class "Default")
      (node (ref "R55") (pin "1") (pinfunction "1_1") (pintype "passive"))
      (node (ref "R56") (pin "2") (pinfunction "2_2") (pintype "passive"))
      (node (ref "U9") (pin "7") (pinfunction "SET_7") (pintype "passive"))
    )
    (net (code "23") (name "Net-(U9-TERM)") (class "Default")
      (node (ref "R55") (pin "2") (pinfunction "2_2") (pintype "passive"))
      (node (ref "U9") (pin "8") (pinfunction "TERM_8") (pintype "passive"))
    )
    (net (code "24") (name "Net-(U9-VCC)") (class "Default")
      (node (ref "C126") (pin "2") (pinfunction "2_2") (pintype "passive"))
      (node (ref "Q8") (pin "5") (pinfunction "S_5") (pintype "passive"))
      (node (ref "Q8") (pin "6") (pinfunction "S_6") (pintype "passive"))
      (node (ref "Q8") (pin "7") (pinfunction "S_7") (pintype "passive"))
      (node (ref "Q8") (pin "8") (pinfunction "S_8") (pintype "passive"))
      (node (ref "Q8") (pin "9") (pinfunction "S_9") (pintype "passive"))
      (node (ref "Q9") (pin "5") (pinfunction "S_5") (pintype "passive"))
      (node (ref "Q9") (pin "6") (pinfunction "S_6") (pintype "passive"))
      (node (ref "Q9") (pin "7") (pinfunction "S_7") (pintype "passive"))
      (node (ref "Q9") (pin "8") (pinfunction "S_8") (pintype "passive"))
      (node (ref "Q9") (pin "9") (pinfunction "S_9") (pintype "passive"))
      (node (ref "U9") (pin "1") (pinfunction "VCC_1") (pintype "passive"))
    )
    (net (code "25") (name "Net-(U11-FB{slash}VSET)") (class "Default")
      (node (ref "R58") (pin "1") (pinfunction "1_1") (pintype "passive"))
      (node (ref "R59") (pin "2") (pinfunction "2_2") (pintype "passive"))
      (node (ref "U11") (pin "9") (pinfunction "FB/VSET_9") (pintype "passive"))
    )
    (net (code "26") (name "Net-(U11-MODE{slash}S-CONF)") (class "Default")
      (node (ref "R61") (pin "1") (pinfunction "1_1") (pintype "passive"))
      (node (ref "R64") (pin "2") (pinfunction "2_2") (pintype "passive"))
      (node (ref "U11") (pin "7") (pinfunction "MODE/S-CONF_7") (pintype "passive"))
    )
    (net (code "27") (name "Net-(U11-SS{slash}TR)") (class "Default")
      (node (ref "C135") (pin "2") (pinfunction "2_2") (pintype "passive"))
      (node (ref "U11") (pin "8") (pinfunction "SS/TR_8") (pintype "passive"))
    )
    (net (code "28") (name "Net-(U11-SW)") (class "Default")
      (node (ref "L10") (pin "1") (pinfunction "1_1") (pintype "passive"))
      (node (ref "U11") (pin "2") (pinfunction "SW_2") (pintype "passive"))
    )
    (net (code "29") (name "Net-(U12-EN)") (class "Default")
      (node (ref "R65") (pin "1") (pinfunction "1_1") (pintype "passive"))
      (node (ref "U12") (pin "6") (pinfunction "EN_6") (pintype "passive"))
    )
    (net (code "30") (name "Net-(U12-SS)") (class "Default")
      (node (ref "C149") (pin "2") (pinfunction "2_2") (pintype "passive"))
      (node (ref "U12") (pin "3") (pinfunction "SS_3") (pintype "passive"))
    )
    (net (code "31") (name "Net-(U12-SW1)") (class "Default")
      (node (ref "C146") (pin "1") (pinfunction "1_1") (pintype "passive"))
      (node (ref "L11") (pin "1") (pinfunction "1_1") (pintype "passive"))
      (node (ref "U12") (pin "10") (pinfunction "SW2_10") (pintype "passive"))
      (node (ref "U12") (pin "11") (pinfunction "SW3_11") (pintype "passive"))
      (node (ref "U12") (pin "9") (pinfunction "SW1_9") (pintype "passive"))
    )
    (net (code "32") (name "Net-(U12-VBST)") (class "Default")
      (node (ref "C146") (pin "2") (pinfunction "2_2") (pintype "passive"))
      (node (ref "U12") (pin "12") (pinfunction "VBST_12") (pintype "passive"))
    )
    (net (code "33") (name "Net-(U12-VFB)") (class "Default")
      (node (ref "C148") (pin "1") (pinfunction "1_1") (pintype "passive"))
      (node (ref "R69") (pin "1") (pinfunction "1_1") (pintype "passive"))
      (node (ref "R75") (pin "2") (pinfunction "2_2") (pintype "passive"))
      (node (ref "U12") (pin "1") (pinfunction "VFB_1") (pintype "passive"))
    )
    (net (code "34") (name "Net-(U12-VREG5)") (class "Default")
      (node (ref "C150") (pin "2") (pinfunction "2_2") (pintype "passive"))
      (node (ref "U12") (pin "2") (pinfunction "VREG5_2") (pintype "passive"))
    )
    (net (code "35") (name "Net-(U13-FB{slash}VSET)") (class "Default")
      (node (ref "R66") (pin "1") (pinfunction "1_1") (pintype "passive"))
      (node (ref "R67") (pin "2") (pinfunction "2_2") (pintype "passive"))
      (node (ref "U13") (pin "9") (pinfunction "FB/VSET_9") (pintype "passive"))
    )
    (net (code "36") (name "Net-(U13-MODE{slash}S-CONF)") (class "Default")
      (node (ref "R71") (pin "1") (pinfunction "1_1") (pintype "passive"))
      (node (ref "R76") (pin "2") (pinfunction "2_2") (pintype "passive"))
      (node (ref "U13") (pin "7") (pinfunction "MODE/S-CONF_7") (pintype "passive"))
    )
    (net (code "37") (name "Net-(U13-SS{slash}TR)") (class "Default")
      (node (ref "C147") (pin "2") (pinfunction "2_2") (pintype "passive"))
      (node (ref "U13") (pin "8") (pinfunction "SS/TR_8") (pintype "passive"))
    )
    (net (code "38") (name "Net-(U13-SW)") (class "Default")
      (node (ref "L12") (pin "1") (pinfunction "1_1") (pintype "passive"))
      (node (ref "U13") (pin "2") (pinfunction "SW_2") (pintype "passive"))
    )
    (net (code "39") (name "VCCINT") (class "Default")
      (node (ref "C120") (pin "1") (pinfunction "1_1") (pintype "passive"))
      (node (ref "C121") (pin "1") (pinfunction "1_1") (pintype "passive"))
      (node (ref "C122") (pin "1") (pinfunction "1_1") (pintype "passive"))
      (node (ref "T1") (pin "1") (pintype "passive"))
      (node (ref "U7") (pin "A8") (pinfunction "OUT_A8") (pintype "passive"))
      (node (ref "U7") (pin "B7") (pinfunction "OUT_B7") (pintype "passive"))
      (node (ref "U7") (pin "B8") (pinfunction "OUT_B8") (pintype "passive"))
      (node (ref "U7") (pin "C7") (pinfunction "OUT_C7") (pintype "passive"))
      (node (ref "U7") (pin "C8") (pinfunction "OUT_C8") (pintype "passive"))
      (node (ref "U7") (pin "D7") (pinfunction "OUT_D7") (pintype "passive"))
      (node (ref "U7") (pin "D8") (pinfunction "OUT_D8") (pintype "passive"))
      (node (ref "U7") (pin "G4") (pinfunction "SENSE+_G4") (pintype "passive"))
    )
    (net (code "40") (name "unconnected-(U7-NC-PadA6)") (class "Default")
      (node (ref "U7") (pin "A6") (pinfunction "NC_A6") (pintype "passive+no_connect"))
    )
    (net (code "41") (name "unconnected-(U7-NC-PadA7)") (class "Default")
      (node (ref "U7") (pin "A7") (pinfunction "NC_A7") (pintype "passive+no_connect"))
    )
    (net (code "42") (name "unconnected-(U7-NC-PadG1)") (class "Default")
      (node (ref "U7") (pin "G1") (pinfunction "NC_G1") (pintype "passive+no_connect"))
    )
    (net (code "43") (name "unconnected-(U7-NC-PadG5)") (class "Default")
      (node (ref "U7") (pin "G5") (pinfunction "NC_G5") (pintype "passive+no_connect"))
    )
    (net (code "44") (name "unconnected-(U7-NC-PadG7)") (class "Default")
      (node (ref "U7") (pin "G7") (pinfunction "NC_G7") (pintype "passive+no_connect"))
    )
    (net (code "45") (name "unconnected-(U7-NC-PadG8)") (class "Default")
      (node (ref "U7") (pin "G8") (pinfunction "NC_G8") (pintype "passive+no_connect"))
    )
    (net (code "46") (name "unconnected-(U7-PMBUS_ALERT-PadA3)") (class "Default")
      (node (ref "U7") (pin "A3") (pinfunction "PMBUS_ALERT_A3") (pintype "passive+no_connect"))
    )
    (net (code "47") (name "unconnected-(U9-*OV-Pad5)") (class "Default")
      (node (ref "U9") (pin "5") (pinfunction "*OV_5") (pintype "passive+no_connect"))
    )
    (net (code "48") (name "unconnected-(U12-PG-Pad5)") (class "Default")
      (node (ref "U12") (pin "5") (pinfunction "PG_5") (pintype "passive+no_connect"))
    )
  )
)
